# power-dist.net
KiCad netlist of a schematic drawn in Altium Designer
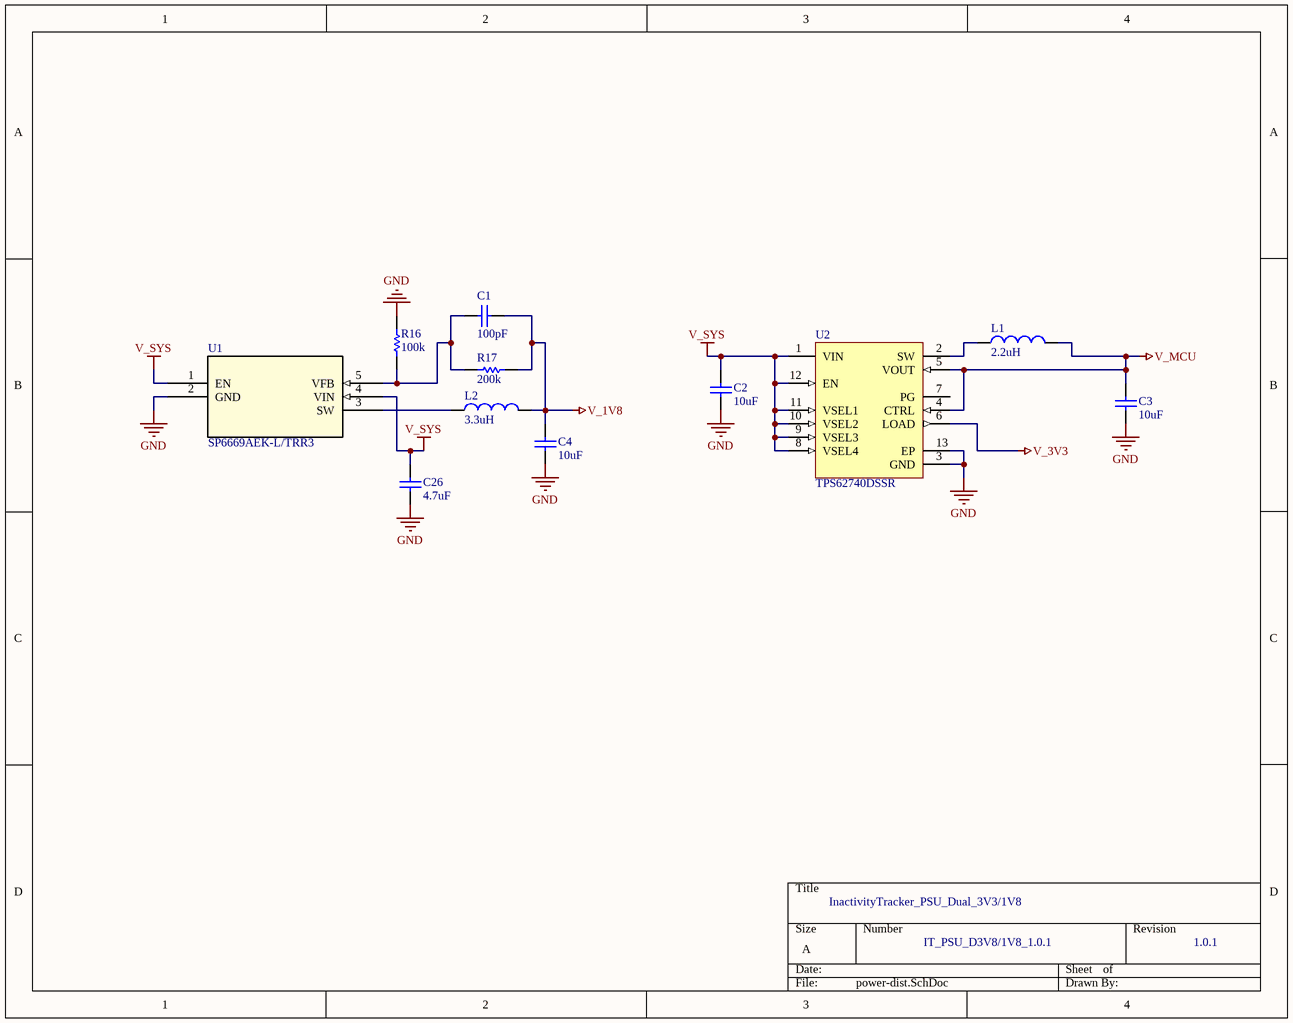
[diagram p0: power-dist.SchDoc]

(export (version "E")
  (design (tool "Eeschema 10.0.6"))
  (components
    (comp (ref "C1")
      (value "100pF")
      (footprint "CAPC1005X55X25ML05T10")
      (fields (field (name "MANUFACTURER") "Murata") (field (name "PART NUMBER") "GRM1555C1H101GA01D"))
      (libsource (lib "Altium Content Vault") (part "CAP"))
    )
    (comp (ref "C2")
      (value "10uF")
      (footprint "CAPC1005X55X25NL05T10")
      (fields (field (name "PART NUMBER") "GRM155R61A105KE15D") (field (name "MANUFACTURER") "Murata"))
      (libsource (lib "Altium Content Vault") (part "CAP"))
    )
    (comp (ref "C3")
      (value "10uF")
      (footprint "CAPC1005X55X25NL05T10")
      (fields (field (name "PART NUMBER") "GRM155R61A105KE15D") (field (name "MANUFACTURER") "Murata"))
      (libsource (lib "Altium Content Vault") (part "CAP"))
    )
    (comp (ref "C4")
      (value "10uF")
      (footprint "CAPC1005X55X25NL05T10")
      (fields (field (name "PART NUMBER") "GRM155R61A105KE15D") (field (name "MANUFACTURER") "Murata"))
      (libsource (lib "Altium Content Vault") (part "CAP"))
    )
    (comp (ref "C26")
      (value "4.7uF")
      (footprint "CAPC1005X55X25NL05T10")
      (fields (field (name "MANUFACTURER") "Murata") (field (name "PART NUMBER") "GRM155R61C102KA01D"))
      (libsource (lib "Altium Content Vault") (part "CAP"))
    )
    (comp (ref "L1")
      (value "2.2uH")
      (footprint "MURA-IND0805_H_0.55_L")
      (description "Chip Inductor, 1.0 uH, +/- 20%, -55 to 125 degC, 2-Pin SMD (0805), RoHS, Tape and Reel")
      (fields (field (name "MANUFACTURER") "Murata"))
      (libsource (lib "Altium Content Vault") (part "IND-2"))
    )
    (comp (ref "L2")
      (value "3.3uH")
      (footprint "InactivityTracker:INDC2012X100N")
      (description "Inductor with Inductance: 3.3uH Tol. +/-30%, Package: 0805 _2012_")
      (fields (field (name "MF") "Murata") (field (name "DIGI-KEY_PART_NUMBER") "490-11718-1-ND"))
      (libsource (lib "InactivityTracker") (part "LQM21PN3R3NGRD"))
    )
    (comp (ref "R16")
      (value "100k")
      (footprint "RESC1005X40X25ML05T05")
      (description "Chip Resistor, 100 KOhm, +/- 1%, 0.63 W, -55 to 155 degC, 0402 (1005 Metric), RoHS, Tape and Reel")
      (fields (field (name "TOLERANCE") "1%"))
      (libsource (lib "Altium Content Vault") (part "RES-2"))
    )
    (comp (ref "R17")
      (value "200k")
      (footprint "RESC1005X40X25ML05T05")
      (fields (field (name "PART NUMBER") "CRCW0402200RFKED") (field (name "MANUFACTURER") "Vishay Dale"))
      (libsource (lib "Altium Content Vault") (part "RES"))
    )
    (comp (ref "U1")
      (value "SP6669AEK-L/TRR3")
      (footprint "SOT-23-5_VAR-AA")
      (description "Buck Switching Regulator IC Positive Adjustable 0.6V 1 Output 600mA SC-74A, SOT-753")
      (fields (field (name "COPYRIGHT") "Copyright (C) 2018 Accelerated Designs. All rights reserved"))
      (libsource (lib "InactivityTracker") (part "SP6669AEK-L/TRR3"))
    )
    (comp (ref "U2")
      (value "TPS62740DSSR")
      (footprint "DSS0012A_V")
      (fields (field (name "PARTNUMBER") "TPS62740"))
      (libsource (lib "Altium Content Vault") (part "TI-TPS62740_2-WSON-12"))
    )
  )
  (nets
    (net (code "1") (name "GND") (class "Default")
      (node (ref "C2") (pin "2") (pinfunction "2_2") (pintype "passive"))
      (node (ref "C26") (pin "2") (pinfunction "2_2") (pintype "passive"))
      (node (ref "C3") (pin "2") (pinfunction "2_2") (pintype "passive"))
      (node (ref "C4") (pin "2") (pinfunction "2_2") (pintype "passive"))
      (node (ref "R16") (pin "1") (pinfunction "1_1") (pintype "passive"))
      (node (ref "U1") (pin "2") (pinfunction "GND_2") (pintype "passive"))
      (node (ref "U2") (pin "13") (pinfunction "EP_13") (pintype "power_in"))
      (node (ref "U2") (pin "3") (pinfunction "GND_3") (pintype "power_in"))
    )
    (net (code "2") (name "Net-(U1-SW)") (class "Default")
      (node (ref "L2") (pin "1") (pinfunction "1_1") (pintype "passive"))
      (node (ref "U1") (pin "3") (pinfunction "SW_3") (pintype "passive"))
    )
    (net (code "3") (name "Net-(U1-VFB)") (class "Default")
      (node (ref "C1") (pin "1") (pinfunction "1_1") (pintype "passive"))
      (node (ref "R16") (pin "2") (pinfunction "2_2") (pintype "passive"))
      (node (ref "R17") (pin "1") (pinfunction "1_1") (pintype "passive"))
      (node (ref "U1") (pin "5") (pinfunction "VFB_5") (pintype "input"))
    )
    (net (code "4") (name "Net-(U2-SW)") (class "Default")
      (node (ref "L1") (pin "1") (pinfunction "1_1") (pintype "passive"))
      (node (ref "U2") (pin "2") (pinfunction "SW_2") (pintype "power_in"))
    )
    (net (code "5") (name "V_1V8") (class "Default")
      (node (ref "C1") (pin "2") (pinfunction "2_2") (pintype "passive"))
      (node (ref "C4") (pin "1") (pinfunction "1_1") (pintype "passive"))
      (node (ref "L2") (pin "2") (pinfunction "2_2") (pintype "passive"))
      (node (ref "R17") (pin "2") (pinfunction "2_2") (pintype "passive"))
    )
    (net (code "6") (name "V_3V3") (class "Default")
      (node (ref "U2") (pin "6") (pinfunction "LOAD_6") (pintype "output"))
    )
    (net (code "7") (name "V_MCU") (class "Default")
      (node (ref "C3") (pin "1") (pinfunction "1_1") (pintype "passive"))
      (node (ref "L1") (pin "2") (pinfunction "2_2") (pintype "passive"))
      (node (ref "U2") (pin "4") (pinfunction "CTRL_4") (pintype "input"))
      (node (ref "U2") (pin "5") (pinfunction "VOUT_5") (pintype "input"))
    )
    (net (code "8") (name "V_SYS") (class "Default")
      (node (ref "C2") (pin "1") (pinfunction "1_1") (pintype "passive"))
      (node (ref "C26") (pin "1") (pinfunction "1_1") (pintype "passive"))
      (node (ref "U1") (pin "1") (pinfunction "EN_1") (pintype "passive"))
      (node (ref "U1") (pin "4") (pinfunction "VIN_4") (pintype "input"))
      (node (ref "U2") (pin "1") (pinfunction "VIN_1") (pintype "power_in"))
      (node (ref "U2") (pin "10") (pinfunction "VSEL2_10") (pintype "input"))
      (node (ref "U2") (pin "11") (pinfunction "VSEL1_11") (pintype "input"))
      (node (ref "U2") (pin "12") (pinfunction "EN_12") (pintype "input"))
      (node (ref "U2") (pin "8") (pinfunction "VSEL4_8") (pintype "input"))
      (node (ref "U2") (pin "9") (pinfunction "VSEL3_9") (pintype "input"))
    )
    (net (code "9") (name "unconnected-(U2-PG-Pad7)") (class "Default")
      (node (ref "U2") (pin "7") (pinfunction "PG_7") (pintype "tri_state"))
    )
  )
)
